# Sheet2.net
KiCad netlist of a schematic drawn in Altium Designer
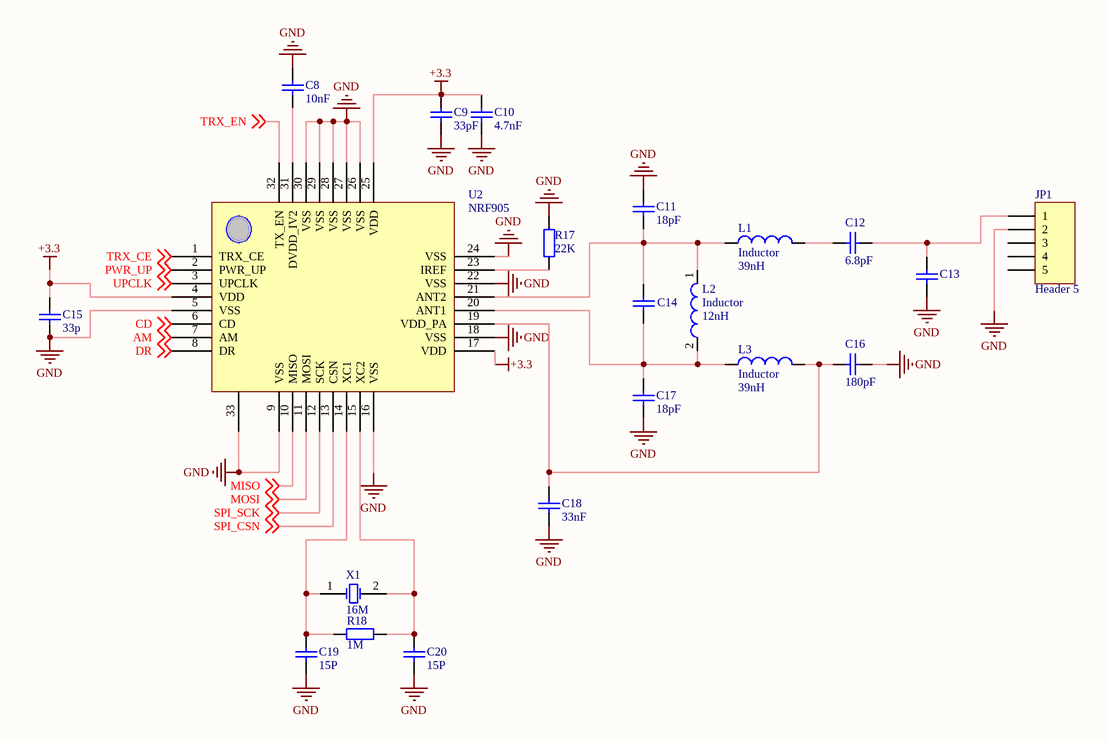
[diagram p0: Sheet2.SchDoc]

(export (version "E")
  (design (tool "Eeschema 10.0.6"))
  (components
    (comp (ref "C8")
      (value "10nF")
      (footprint "0603C")
      (description "Capacitor")
      (fields (field (name "PUBLISHER") "Altium Limited"))
      (libsource (lib "ECG2.0") (part "Cap"))
    )
    (comp (ref "C9")
      (value "33pF")
      (footprint "0603C")
      (description "Capacitor")
      (fields (field (name "PUBLISHER") "Altium Limited"))
      (libsource (lib "ECG2.0") (part "Cap"))
    )
    (comp (ref "C10")
      (value "4.7nF")
      (footprint "0603C")
      (description "Capacitor")
      (fields (field (name "PUBLISHER") "Altium Limited"))
      (libsource (lib "ECG2.0") (part "Cap"))
    )
    (comp (ref "C11")
      (value "18pF")
      (footprint "0603C")
      (description "Capacitor")
      (fields (field (name "PUBLISHER") "Altium Limited"))
      (libsource (lib "ECG2.0") (part "Cap"))
    )
    (comp (ref "C12")
      (value "6.8pF")
      (footprint "0603C")
      (description "Capacitor")
      (fields (field (name "PUBLISHER") "Altium Limited"))
      (libsource (lib "ECG2.0") (part "Cap"))
    )
    (comp (ref "C13")
      (value "~")
      (footprint "0603C")
      (description "Capacitor")
      (fields (field (name "PUBLISHER") "Altium Limited"))
      (libsource (lib "ECG2.0") (part "Cap"))
    )
    (comp (ref "C14")
      (value "~")
      (footprint "0603C")
      (description "Capacitor")
      (fields (field (name "PUBLISHER") "Altium Limited"))
      (libsource (lib "ECG2.0") (part "Cap"))
    )
    (comp (ref "C15")
      (value "33p")
      (footprint "0603C")
      (description "Capacitor")
      (fields (field (name "PUBLISHER") "Altium Limited"))
      (libsource (lib "ECG2.0") (part "Cap"))
    )
    (comp (ref "C16")
      (value "180pF")
      (footprint "0603C")
      (description "Capacitor")
      (fields (field (name "PUBLISHER") "Altium Limited"))
      (libsource (lib "ECG2.0") (part "Cap"))
    )
    (comp (ref "C17")
      (value "18pF")
      (footprint "0603C")
      (description "Capacitor")
      (fields (field (name "PUBLISHER") "Altium Limited"))
      (libsource (lib "ECG2.0") (part "Cap"))
    )
    (comp (ref "C18")
      (value "33nF")
      (footprint "0603C")
      (description "Capacitor")
      (fields (field (name "PUBLISHER") "Altium Limited"))
      (libsource (lib "ECG") (part "Cap"))
    )
    (comp (ref "C19")
      (value "15P")
      (footprint "0603C")
      (description "Capacitor")
      (fields (field (name "PUBLISHER") "Altium Limited"))
      (libsource (lib "ECG") (part "Cap"))
    )
    (comp (ref "C20")
      (value "15P")
      (footprint "0603C")
      (description "Capacitor")
      (fields (field (name "PUBLISHER") "Altium Limited"))
      (libsource (lib "ECG") (part "Cap"))
    )
    (comp (ref "JP1")
      (value "Header 5")
      (footprint "SMA")
      (description "Header, 5-Pin")
      (fields (field (name "PUBLISHER") "Altium Limited"))
      (libsource (lib "Miscellaneous Connectors") (part "Header 5"))
    )
    (comp (ref "L1")
      (value "Inductor")
      (footprint "0603")
      (fields (field (name "ALTIUM_VALUE") "39nH") (field (name "PUBLISHER") "Altium Limited"))
      (libsource (lib "Miscellaneous Devices") (part "Inductor"))
    )
    (comp (ref "L2")
      (value "Inductor")
      (footprint "ECG2.0:0603")
      (fields (field (name "ALTIUM_VALUE") "12nH") (field (name "PUBLISHER") "Altium Limited"))
      (libsource (lib "") (part "Inductor_1"))
    )
    (comp (ref "L3")
      (value "Inductor")
      (footprint "0603")
      (fields (field (name "ALTIUM_VALUE") "39nH") (field (name "PUBLISHER") "Altium Limited"))
      (libsource (lib "Miscellaneous Devices") (part "Inductor"))
    )
    (comp (ref "R17")
      (value "22K")
      (footprint "0603R")
      (description "Resistor")
      (fields (field (name "PUBLISHER") "Altium Limited"))
      (libsource (lib "ECG2.0") (part "Res2"))
    )
    (comp (ref "R18")
      (value "1M")
      (footprint "0603R")
      (description "Resistor")
      (fields (field (name "PUBLISHER") "Altium Limited"))
      (libsource (lib "ECG") (part "Res2"))
    )
    (comp (ref "U2") (value "NRF905") (footprint "QFN32_M") (libsource (lib "ECG2.0") (part "NRF905")))
    (comp (ref "X1")
      (value "16M")
      (footprint "CY2")
      (description "Crystal Oscillator")
      (fields (field (name "PUBLISHER") "Altium Limited"))
      (libsource (lib "Miscellaneous Devices") (part "XTAL"))
    )
  )
  (nets
    (net (code "1") (name "+3.3") (class "Default")
      (node (ref "C10") (pin "2") (pinfunction "2_2") (pintype "passive"))
      (node (ref "C15") (pin "2") (pinfunction "2_2") (pintype "passive"))
      (node (ref "C9") (pin "2") (pinfunction "2_2") (pintype "passive"))
      (node (ref "U2") (pin "17") (pinfunction "VDD_17") (pintype "passive"))
      (node (ref "U2") (pin "25") (pinfunction "VDD_25") (pintype "passive"))
      (node (ref "U2") (pin "4") (pinfunction "VDD_4") (pintype "passive"))
    )
    (net (code "2") (name "AM") (class "Default")
      (node (ref "U2") (pin "7") (pinfunction "AM_7") (pintype "passive"))
    )
    (net (code "3") (name "CD") (class "Default")
      (node (ref "U2") (pin "6") (pinfunction "CD_6") (pintype "passive"))
    )
    (net (code "4") (name "DR") (class "Default")
      (node (ref "U2") (pin "8") (pinfunction "DR_8") (pintype "passive"))
    )
    (net (code "5") (name "GND") (class "Default")
      (node (ref "C10") (pin "1") (pinfunction "1_1") (pintype "passive"))
      (node (ref "C11") (pin "2") (pinfunction "2_2") (pintype "passive"))
      (node (ref "C13") (pin "1") (pinfunction "1_1") (pintype "passive"))
      (node (ref "C15") (pin "1") (pinfunction "1_1") (pintype "passive"))
      (node (ref "C16") (pin "1") (pinfunction "1_1") (pintype "passive"))
      (node (ref "C17") (pin "1") (pinfunction "1_1") (pintype "passive"))
      (node (ref "C18") (pin "1") (pinfunction "1_1") (pintype "passive"))
      (node (ref "C19") (pin "1") (pinfunction "1_1") (pintype "passive"))
      (node (ref "C20") (pin "1") (pinfunction "1_1") (pintype "passive"))
      (node (ref "C8") (pin "2") (pinfunction "2_2") (pintype "passive"))
      (node (ref "C9") (pin "1") (pinfunction "1_1") (pintype "passive"))
      (node (ref "JP1") (pin "2") (pinfunction "2_2") (pintype "passive"))
      (node (ref "R17") (pin "2") (pinfunction "2_2") (pintype "passive"))
      (node (ref "U2") (pin "16") (pinfunction "VSS_16") (pintype "passive"))
      (node (ref "U2") (pin "18") (pinfunction "VSS_18") (pintype "passive"))
      (node (ref "U2") (pin "22") (pinfunction "VSS_22") (pintype "passive"))
      (node (ref "U2") (pin "24") (pinfunction "VSS_24") (pintype "passive"))
      (node (ref "U2") (pin "26") (pinfunction "VSS_26") (pintype "passive"))
      (node (ref "U2") (pin "27") (pinfunction "VSS_27") (pintype "passive"))
      (node (ref "U2") (pin "28") (pinfunction "VSS_28") (pintype "passive"))
      (node (ref "U2") (pin "29") (pinfunction "VSS_29") (pintype "passive"))
      (node (ref "U2") (pin "30") (pinfunction "VSS_30") (pintype "passive"))
      (node (ref "U2") (pin "33") (pinfunction "33_33") (pintype "passive"))
      (node (ref "U2") (pin "5") (pinfunction "VSS_5") (pintype "passive"))
      (node (ref "U2") (pin "9") (pinfunction "VSS_9") (pintype "passive"))
    )
    (net (code "6") (name "MISO") (class "Default")
      (node (ref "U2") (pin "10") (pinfunction "MISO_10") (pintype "passive"))
    )
    (net (code "7") (name "MOSI") (class "Default")
      (node (ref "U2") (pin "11") (pinfunction "MOSI_11") (pintype "passive"))
    )
    (net (code "8") (name "Net-(C12-Pad1)") (class "Default")
      (node (ref "C12") (pin "1") (pinfunction "1_1") (pintype "passive"))
      (node (ref "C13") (pin "2") (pinfunction "2_2") (pintype "passive"))
      (node (ref "JP1") (pin "1") (pinfunction "1_1") (pintype "passive"))
    )
    (net (code "9") (name "Net-(C12-Pad2)") (class "Default")
      (node (ref "C12") (pin "2") (pinfunction "2_2") (pintype "passive"))
      (node (ref "L1") (pin "2") (pinfunction "2_2") (pintype "passive"))
    )
    (net (code "10") (name "Net-(U2-ANT1)") (class "Default")
      (node (ref "C14") (pin "1") (pinfunction "1_1") (pintype "passive"))
      (node (ref "C17") (pin "2") (pinfunction "2_2") (pintype "passive"))
      (node (ref "L2") (pin "2") (pinfunction "2_2") (pintype "passive"))
      (node (ref "L3") (pin "1") (pinfunction "1_1") (pintype "passive"))
      (node (ref "U2") (pin "20") (pinfunction "ANT1_20") (pintype "passive"))
    )
    (net (code "11") (name "Net-(U2-ANT2)") (class "Default")
      (node (ref "C11") (pin "1") (pinfunction "1_1") (pintype "passive"))
      (node (ref "C14") (pin "2") (pinfunction "2_2") (pintype "passive"))
      (node (ref "L1") (pin "1") (pinfunction "1_1") (pintype "passive"))
      (node (ref "L2") (pin "1") (pinfunction "1_1") (pintype "passive"))
      (node (ref "U2") (pin "21") (pinfunction "ANT2_21") (pintype "passive"))
    )
    (net (code "12") (name "Net-(U2-DVDD_IV2)") (class "Default")
      (node (ref "C8") (pin "1") (pinfunction "1_1") (pintype "passive"))
      (node (ref "U2") (pin "31") (pinfunction "DVDD_IV2_31") (pintype "passive"))
    )
    (net (code "13") (name "Net-(U2-IREF)") (class "Default")
      (node (ref "R17") (pin "1") (pinfunction "1_1") (pintype "passive"))
      (node (ref "U2") (pin "23") (pinfunction "IREF_23") (pintype "passive"))
    )
    (net (code "14") (name "Net-(U2-VDD_PA)") (class "Default")
      (node (ref "C16") (pin "2") (pinfunction "2_2") (pintype "passive"))
      (node (ref "C18") (pin "2") (pinfunction "2_2") (pintype "passive"))
      (node (ref "L3") (pin "2") (pinfunction "2_2") (pintype "passive"))
      (node (ref "U2") (pin "19") (pinfunction "VDD_PA_19") (pintype "passive"))
    )
    (net (code "15") (name "Net-(U2-XC1)") (class "Default")
      (node (ref "C19") (pin "2") (pinfunction "2_2") (pintype "passive"))
      (node (ref "R18") (pin "1") (pinfunction "1_1") (pintype "passive"))
      (node (ref "U2") (pin "14") (pinfunction "XC1_14") (pintype "passive"))
      (node (ref "X1") (pin "1") (pinfunction "OSC1_1") (pintype "passive"))
    )
    (net (code "16") (name "Net-(U2-XC2)") (class "Default")
      (node (ref "C20") (pin "2") (pinfunction "2_2") (pintype "passive"))
      (node (ref "R18") (pin "2") (pinfunction "2_2") (pintype "passive"))
      (node (ref "U2") (pin "15") (pinfunction "XC2_15") (pintype "passive"))
      (node (ref "X1") (pin "2") (pinfunction "OSC2_2") (pintype "passive"))
    )
    (net (code "17") (name "PWR_UP") (class "Default")
      (node (ref "U2") (pin "2") (pinfunction "PWR_UP_2") (pintype "passive"))
    )
    (net (code "18") (name "SPI_CSN") (class "Default")
      (node (ref "U2") (pin "13") (pinfunction "CSN_13") (pintype "passive"))
    )
    (net (code "19") (name "SPI_SCK") (class "Default")
      (node (ref "U2") (pin "12") (pinfunction "SCK_12") (pintype "passive"))
    )
    (net (code "20") (name "TRX_CE") (class "Default")
      (node (ref "U2") (pin "1") (pinfunction "TRX_CE_1") (pintype "passive"))
    )
    (net (code "21") (name "TRX_EN") (class "Default")
      (node (ref "U2") (pin "32") (pinfunction "TX_EN_32") (pintype "passive"))
    )
    (net (code "22") (name "UPCLK") (class "Default")
      (node (ref "U2") (pin "3") (pinfunction "UPCLK_3") (pintype "passive"))
    )
    (net (code "23") (name "unconnected-(JP1-Pad3)") (class "Default")
      (node (ref "JP1") (pin "3") (pinfunction "3_3") (pintype "passive"))
    )
    (net (code "24") (name "unconnected-(JP1-Pad4)") (class "Default")
      (node (ref "JP1") (pin "4") (pinfunction "4_4") (pintype "passive"))
    )
    (net (code "25") (name "unconnected-(JP1-Pad5)") (class "Default")
      (node (ref "JP1") (pin "5") (pinfunction "5_5") (pintype "passive"))
    )
  )
)
